# Computer_Power_Relay_-_Merge.net
KiCad netlist of a schematic drawn in EAGLE
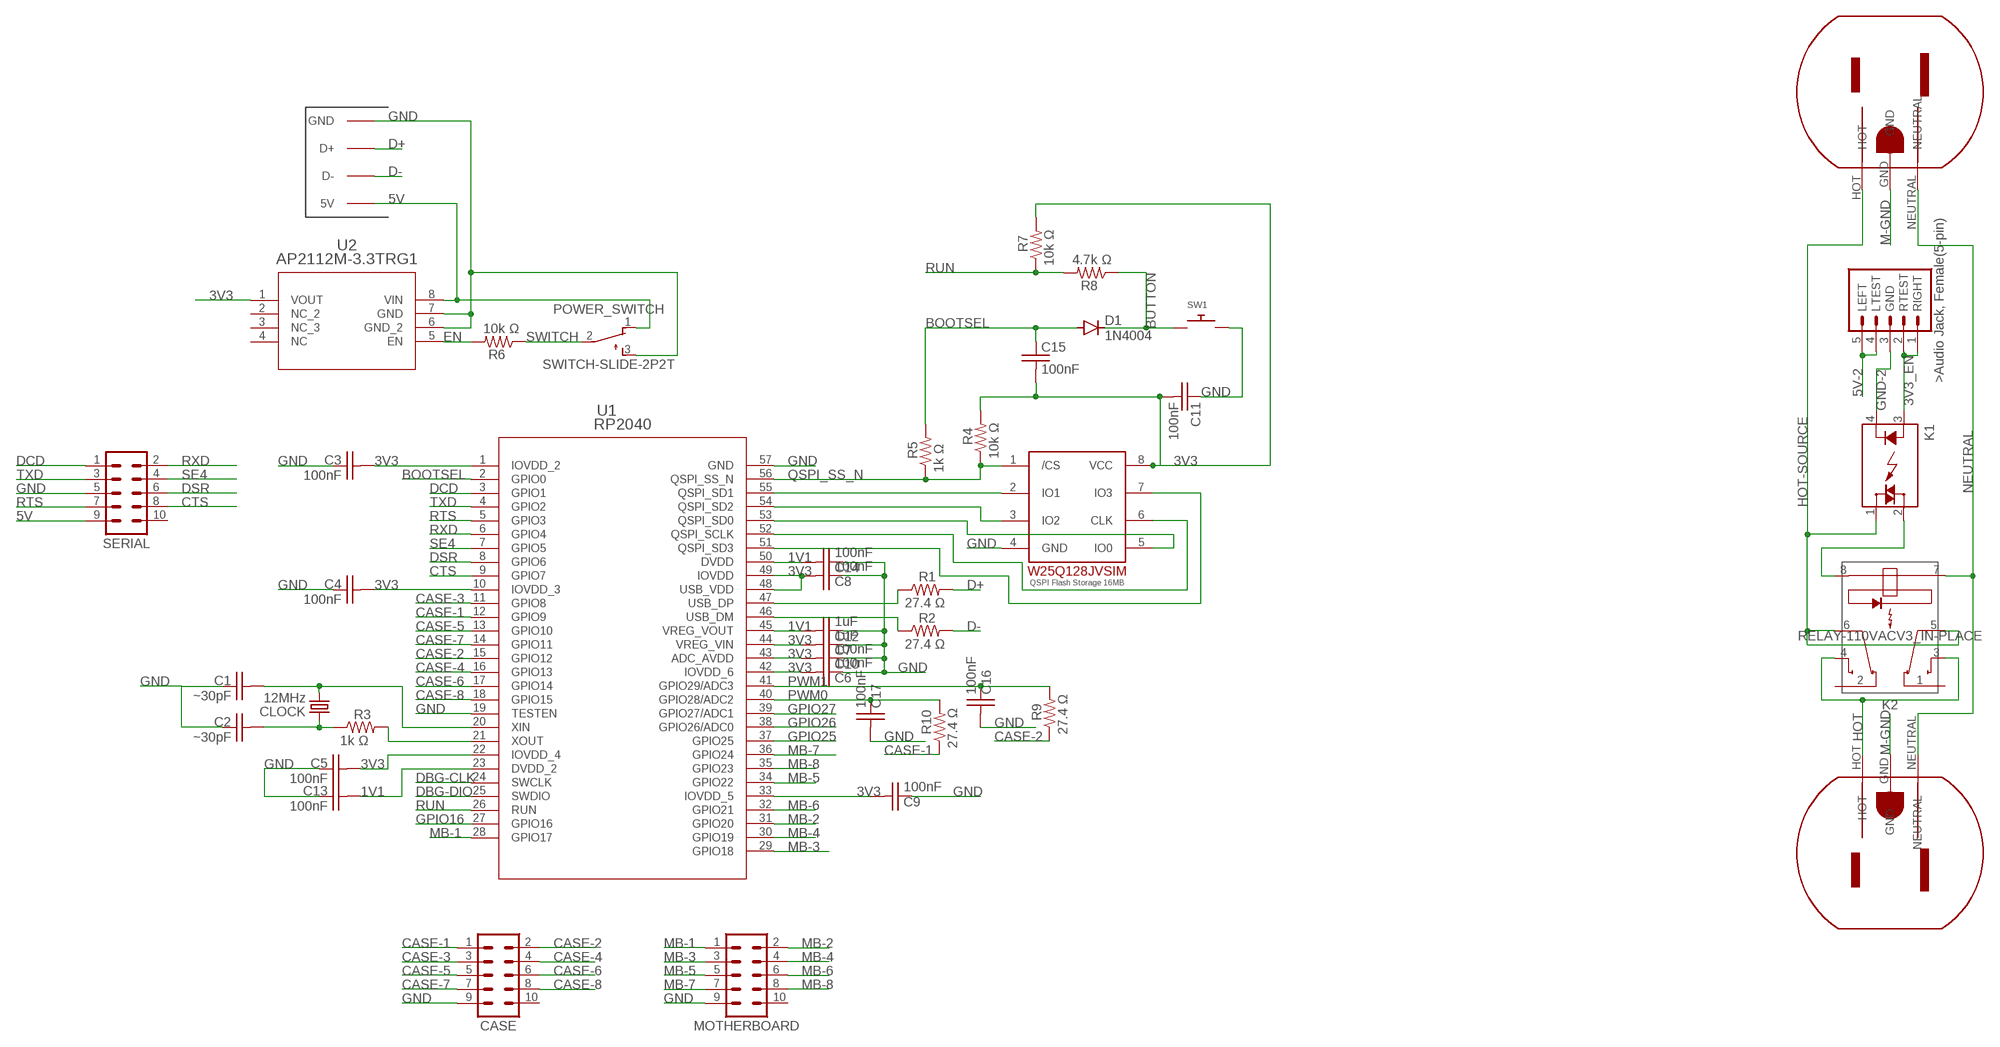
[diagram p0: schematic, sheet 1]

(export (version "E")
  (design (tool "Eeschema 10.0.6"))
  (components
    (comp (ref "C1")
      (value "~30pF")
      (footprint "eagle-import:C0402K")
      (libsource (lib "eagle-import") (part "CAP-NONPOL-USC0402K"))
    )
    (comp (ref "C2")
      (value "~30pF")
      (footprint "eagle-import:C0402K")
      (libsource (lib "eagle-import") (part "CAP-NONPOL-USC0402K"))
    )
    (comp (ref "C3")
      (value "100nF")
      (footprint "eagle-import:C0402K")
      (libsource (lib "eagle-import") (part "CAP-NONPOL-USC0402K"))
    )
    (comp (ref "C4")
      (value "100nF")
      (footprint "eagle-import:C0402K")
      (libsource (lib "eagle-import") (part "CAP-NONPOL-USC0402K"))
    )
    (comp (ref "C5")
      (value "100nF")
      (footprint "eagle-import:C0402K")
      (libsource (lib "eagle-import") (part "CAP-NONPOL-USC0402K"))
    )
    (comp (ref "C6")
      (value "100nF")
      (footprint "eagle-import:C0402K")
      (libsource (lib "eagle-import") (part "CAP-NONPOL-USC0402K"))
    )
    (comp (ref "C7")
      (value "1uF")
      (footprint "eagle-import:C0402K")
      (libsource (lib "eagle-import") (part "CAP-NONPOL-USC0402K"))
    )
    (comp (ref "C8")
      (value "100nF")
      (footprint "eagle-import:C0402K")
      (libsource (lib "eagle-import") (part "CAP-NONPOL-USC0402K"))
    )
    (comp (ref "C9")
      (value "100nF")
      (footprint "eagle-import:C0402K")
      (libsource (lib "eagle-import") (part "CAP-NONPOL-USC0402K"))
    )
    (comp (ref "C10")
      (value "100nF")
      (footprint "eagle-import:C0402K")
      (libsource (lib "eagle-import") (part "CAP-NONPOL-USC0402K"))
    )
    (comp (ref "C11")
      (value "100nF")
      (footprint "eagle-import:C0402K")
      (libsource (lib "eagle-import") (part "CAP-NONPOL-USC0402K"))
    )
    (comp (ref "C12")
      (value "1uF")
      (footprint "eagle-import:C0402K")
      (libsource (lib "eagle-import") (part "CAP-NONPOL-USC0402K"))
    )
    (comp (ref "C13")
      (value "100nF")
      (footprint "eagle-import:C0402K")
      (libsource (lib "eagle-import") (part "CAP-NONPOL-USC0402K"))
    )
    (comp (ref "C14")
      (value "100nF")
      (footprint "eagle-import:C0402K")
      (libsource (lib "eagle-import") (part "CAP-NONPOL-USC0402K"))
    )
    (comp (ref "C15")
      (value "100nF")
      (footprint "eagle-import:C0402K")
      (libsource (lib "eagle-import") (part "CAP-NONPOL-USC0402K"))
    )
    (comp (ref "C16")
      (value "100nF")
      (footprint "eagle-import:C0402K")
      (libsource (lib "eagle-import") (part "CAP-NONPOL-USC0402K"))
    )
    (comp (ref "C17")
      (value "100nF")
      (footprint "eagle-import:C0402K")
      (libsource (lib "eagle-import") (part "CAP-NONPOL-USC0402K"))
    )
    (comp (ref "CASE")
      (value "MA05-2")
      (footprint "eagle-import:MA05-2")
      (libsource (lib "eagle-import") (part "MA05-2"))
    )
    (comp (ref "CLOCK")
      (value "12MHz")
      (footprint "eagle-import:HC49_S")
      (libsource (lib "eagle-import") (part "CRYSTALHC49S"))
    )
    (comp (ref "D1")
      (value "1N4004")
      (footprint "eagle-import:DO41-10")
      (libsource (lib "eagle-import") (part "1N4004"))
    )
    (comp (ref "K1")
      (value "RELAY-3V3DC-110VAC012")
      (footprint "eagle-import:RELAY-3V3-110V")
      (fields (field (name "MPN") "ACV33012"))
      (libsource (lib "eagle-import") (part "RELAY-3V3DC-110VAC012"))
    )
    (comp (ref "K2")
      (value "RELAY-110VACV3_IN-PLACE")
      (footprint "eagle-import:RELAY-110VAC-V3")
      (libsource (lib "eagle-import") (part "RELAY-110VACV3_IN-PLACE"))
    )
    (comp (ref "MOTHERBOARD")
      (value "MA05-2")
      (footprint "eagle-import:MA05-2")
      (libsource (lib "eagle-import") (part "MA05-2"))
    )
    (comp (ref "POWER_SWITCH")
      (value "SWITCH-SLIDE-2P2T")
      (footprint "eagle-import:SWITCH-SLIDE-2P2T")
      (libsource (lib "eagle-import") (part "SWITCH-SLIDE-2P2T"))
    )
    (comp (ref "R1")
      (value "27.4 Ω")
      (footprint "eagle-import:R0603")
      (libsource (lib "eagle-import") (part "R-US_R0603"))
    )
    (comp (ref "R2")
      (value "27.4 Ω")
      (footprint "eagle-import:R0603")
      (libsource (lib "eagle-import") (part "R-US_R0603"))
    )
    (comp (ref "R3")
      (value "1k Ω")
      (footprint "eagle-import:R0603")
      (libsource (lib "eagle-import") (part "R-US_R0603"))
    )
    (comp (ref "R4")
      (value "10k Ω")
      (footprint "eagle-import:R0603")
      (libsource (lib "eagle-import") (part "R-US_R0603"))
    )
    (comp (ref "R5")
      (value "1k Ω")
      (footprint "eagle-import:R0603")
      (libsource (lib "eagle-import") (part "R-US_R0603"))
    )
    (comp (ref "R6")
      (value "10k Ω")
      (footprint "eagle-import:R0603")
      (libsource (lib "eagle-import") (part "R-US_R0603"))
    )
    (comp (ref "R7")
      (value "10k Ω")
      (footprint "eagle-import:R0603")
      (libsource (lib "eagle-import") (part "R-US_R0603"))
    )
    (comp (ref "R8")
      (value "4.7k Ω")
      (footprint "eagle-import:R0603")
      (libsource (lib "eagle-import") (part "R-US_R0603"))
    )
    (comp (ref "R9")
      (value "27.4 Ω")
      (footprint "eagle-import:R0603")
      (libsource (lib "eagle-import") (part "R-US_R0603"))
    )
    (comp (ref "R10")
      (value "27.4 Ω")
      (footprint "eagle-import:R0603")
      (libsource (lib "eagle-import") (part "R-US_R0603"))
    )
    (comp (ref "SERIAL")
      (value "MA05-2")
      (footprint "eagle-import:MA05-2")
      (libsource (lib "eagle-import") (part "MA05-2"))
    )
    (comp (ref "SW1")
      (value "SWITCH_PUSHBUTTONSOFTTOUCHSMD_SJ")
      (footprint "eagle-import:PUSHBUTTON_TH")
      (libsource (lib "eagle-import") (part "SWITCH_PUSHBUTTONSOFTTOUCHSMD_SJ"))
    )
    (comp (ref "U$1")
      (value "W25Q128JVSIM-ND__QSPI-FLASH")
      (footprint "eagle-import:SO08")
      (libsource (lib "eagle-import") (part "W25Q128JVSIM-ND__QSPI-FLASH"))
    )
    (comp (ref "U$2")
      (value "PCB_USB")
      (footprint "eagle-import:PCB_USB")
      (libsource (lib "eagle-import") (part "PCB_USB"))
    )
    (comp (ref "U$3")
      (value "MAINS-POWER-OUTLET3-PIN")
      (footprint "eagle-import:3-PIN-POWER")
      (libsource (lib "eagle-import") (part "MAINS-POWER-OUTLET3-PIN"))
    )
    (comp (ref "U$4")
      (value "MAINS-POWER-OUTLET3-PIN")
      (footprint "eagle-import:3-PIN-POWER")
      (libsource (lib "eagle-import") (part "MAINS-POWER-OUTLET3-PIN"))
    )
    (comp (ref "U$5")
      (value "AUDIO_JACK_FEMALE_5-PIN")
      (footprint "eagle-import:AUDIO_JACK_FEMALE_5-PIN")
      (libsource (lib "eagle-import") (part "AUDIO_JACK_FEMALE_5-PIN"))
    )
    (comp (ref "U1")
      (value "RP2040")
      (footprint "eagle-import:IC57_RP2040")
      (fields
        (field (name "MANUFACTURER_PART_NUMBER") "SC0908(7)")
        (field (name "COPYRIGHT") "Copyright (C) 2022 Ultra Librarian. All rights reserved.")
      )
      (libsource (lib "eagle-import") (part "RP2040"))
    )
    (comp (ref "U2")
      (value "AP2112M-3.3TRG1")
      (footprint "eagle-import:AP2112M-3.3TRG1_DIO")
      (fields (field (name "COPYRIGHT") "Copyright (C) 2022 Ultra Librarian. All rights reserved."))
      (libsource (lib "eagle-import") (part "AP2112M-3.3TRG1"))
    )
  )
  (nets
    (net (code "1") (name "/1V1") (class "Default")
      (node (ref "C12") (pin "2") (pinfunction "2_2") (pintype "passive"))
      (node (ref "C13") (pin "2") (pinfunction "2_2") (pintype "passive"))
      (node (ref "C14") (pin "2") (pinfunction "2_2") (pintype "passive"))
      (node (ref "U1") (pin "23") (pinfunction "DVDD_2_23") (pintype "power_in"))
      (node (ref "U1") (pin "45") (pinfunction "VREG_VOUT_45") (pintype "output"))
      (node (ref "U1") (pin "50") (pinfunction "DVDD_50") (pintype "power_in"))
    )
    (net (code "2") (name "/3V3") (class "Default")
      (node (ref "C10") (pin "2") (pinfunction "2_2") (pintype "passive"))
      (node (ref "C11") (pin "2") (pinfunction "2_2") (pintype "passive"))
      (node (ref "C15") (pin "2") (pinfunction "2_2") (pintype "passive"))
      (node (ref "C3") (pin "2") (pinfunction "2_2") (pintype "passive"))
      (node (ref "C4") (pin "2") (pinfunction "2_2") (pintype "passive"))
      (node (ref "C5") (pin "2") (pinfunction "2_2") (pintype "passive"))
      (node (ref "C6") (pin "2") (pinfunction "2_2") (pintype "passive"))
      (node (ref "C7") (pin "2") (pinfunction "2_2") (pintype "passive"))
      (node (ref "C8") (pin "2") (pinfunction "2_2") (pintype "passive"))
      (node (ref "C9") (pin "2") (pinfunction "2_2") (pintype "passive"))
      (node (ref "R4") (pin "2") (pinfunction "2_2") (pintype "passive"))
      (node (ref "R7") (pin "2") (pinfunction "2_2") (pintype "passive"))
      (node (ref "U$1") (pin "8") (pinfunction "VCC_8") (pintype "power_in"))
      (node (ref "U1") (pin "1") (pinfunction "IOVDD_2_1") (pintype "power_in"))
      (node (ref "U1") (pin "10") (pinfunction "IOVDD_3_10") (pintype "power_in"))
      (node (ref "U1") (pin "22") (pinfunction "IOVDD_4_22") (pintype "power_in"))
      (node (ref "U1") (pin "33") (pinfunction "IOVDD_5_33") (pintype "power_in"))
      (node (ref "U1") (pin "42") (pinfunction "IOVDD_6_42") (pintype "power_in"))
      (node (ref "U1") (pin "43") (pinfunction "ADC_AVDD_43") (pintype "power_in"))
      (node (ref "U1") (pin "44") (pinfunction "VREG_VIN_44") (pintype "passive"))
      (node (ref "U1") (pin "48") (pinfunction "USB_VDD_48") (pintype "power_in"))
      (node (ref "U1") (pin "49") (pinfunction "IOVDD_49") (pintype "power_in"))
      (node (ref "U2") (pin "1") (pinfunction "VOUT_1") (pintype "output"))
    )
    (net (code "3") (name "/3V3_EN") (class "Default")
      (node (ref "K1") (pin "3") (pinfunction "3_3") (pintype "passive"))
      (node (ref "U$5") (pin "1") (pinfunction "RIGHT_1") (pintype "input"))
      (node (ref "U$5") (pin "2") (pinfunction "RTEST_2") (pintype "output"))
    )
    (net (code "4") (name "/5V") (class "Default")
      (node (ref "POWER_SWITCH") (pin "1") (pinfunction "O_1") (pintype "passive"))
      (node (ref "SERIAL") (pin "9") (pinfunction "9_9") (pintype "passive"))
      (node (ref "U$2") (pin "5V") (pinfunction "5V_5V") (pintype "bidirectional"))
      (node (ref "U$2") (pin "5V_2") (pinfunction "5V_5V_2") (pintype "bidirectional"))
      (node (ref "U2") (pin "8") (pinfunction "VIN_8") (pintype "power_in"))
    )
    (net (code "5") (name "/5V-2") (class "Default")
      (node (ref "U$5") (pin "4") (pinfunction "LTEST_4") (pintype "output"))
      (node (ref "U$5") (pin "5") (pinfunction "LEFT_5") (pintype "input"))
    )
    (net (code "6") (name "/BOOTSEL") (class "Default")
      (node (ref "C15") (pin "1") (pinfunction "1_1") (pintype "passive"))
      (node (ref "D1") (pin "A") (pinfunction "A_A") (pintype "passive"))
      (node (ref "R5") (pin "2") (pinfunction "2_2") (pintype "passive"))
      (node (ref "U1") (pin "2") (pinfunction "GPIO0_2") (pintype "bidirectional"))
    )
    (net (code "7") (name "/BUTTON") (class "Default")
      (node (ref "D1") (pin "C") (pinfunction "C_C") (pintype "passive"))
      (node (ref "R8") (pin "1") (pinfunction "1_1") (pintype "passive"))
      (node (ref "SW1") (pin "P$1") (pinfunction "P$1_P$1") (pintype "passive"))
    )
    (net (code "8") (name "/CASE-1") (class "Default")
      (node (ref "CASE") (pin "1") (pinfunction "1_1") (pintype "passive"))
      (node (ref "R10") (pin "1") (pinfunction "1_1") (pintype "passive"))
      (node (ref "U1") (pin "12") (pinfunction "GPIO9_12") (pintype "bidirectional"))
    )
    (net (code "9") (name "/CASE-2") (class "Default")
      (node (ref "CASE") (pin "2") (pinfunction "2_2") (pintype "passive"))
      (node (ref "R9") (pin "1") (pinfunction "1_1") (pintype "passive"))
      (node (ref "U1") (pin "15") (pinfunction "GPIO12_15") (pintype "bidirectional"))
    )
    (net (code "10") (name "/CASE-3") (class "Default")
      (node (ref "CASE") (pin "3") (pinfunction "3_3") (pintype "passive"))
      (node (ref "U1") (pin "11") (pinfunction "GPIO8_11") (pintype "bidirectional"))
    )
    (net (code "11") (name "/CASE-4") (class "Default")
      (node (ref "CASE") (pin "4") (pinfunction "4_4") (pintype "passive"))
      (node (ref "U1") (pin "16") (pinfunction "GPIO13_16") (pintype "bidirectional"))
    )
    (net (code "12") (name "/CASE-5") (class "Default")
      (node (ref "CASE") (pin "5") (pinfunction "5_5") (pintype "passive"))
      (node (ref "U1") (pin "13") (pinfunction "GPIO10_13") (pintype "bidirectional"))
    )
    (net (code "13") (name "/CASE-6") (class "Default")
      (node (ref "CASE") (pin "6") (pinfunction "6_6") (pintype "passive"))
      (node (ref "U1") (pin "17") (pinfunction "GPIO14_17") (pintype "bidirectional"))
    )
    (net (code "14") (name "/CASE-7") (class "Default")
      (node (ref "CASE") (pin "7") (pinfunction "7_7") (pintype "passive"))
      (node (ref "U1") (pin "14") (pinfunction "GPIO11_14") (pintype "bidirectional"))
    )
    (net (code "15") (name "/CASE-8") (class "Default")
      (node (ref "CASE") (pin "8") (pinfunction "8_8") (pintype "passive"))
      (node (ref "U1") (pin "18") (pinfunction "GPIO15_18") (pintype "bidirectional"))
    )
    (net (code "16") (name "/CTS") (class "Default")
      (node (ref "SERIAL") (pin "8") (pinfunction "8_8") (pintype "passive"))
      (node (ref "U1") (pin "9") (pinfunction "GPIO7_9") (pintype "bidirectional"))
    )
    (net (code "17") (name "/D+") (class "Default")
      (node (ref "R1") (pin "2") (pinfunction "2_2") (pintype "passive"))
      (node (ref "U$2") (pin "D+") (pinfunction "D+_D+") (pintype "bidirectional"))
      (node (ref "U$2") (pin "D+_2") (pinfunction "D+_D+_2") (pintype "bidirectional"))
    )
    (net (code "18") (name "/D-") (class "Default")
      (node (ref "R2") (pin "2") (pinfunction "2_2") (pintype "passive"))
      (node (ref "U$2") (pin "D-") (pinfunction "D-_D-") (pintype "bidirectional"))
      (node (ref "U$2") (pin "D-_2") (pinfunction "D-_D-_2") (pintype "bidirectional"))
    )
    (net (code "19") (name "/DBG-CLK") (class "Default")
      (node (ref "U1") (pin "24") (pinfunction "SWCLK_24") (pintype "passive"))
    )
    (net (code "20") (name "/DBG-DIO") (class "Default")
      (node (ref "U1") (pin "25") (pinfunction "SWDIO_25") (pintype "passive"))
    )
    (net (code "21") (name "/DCD") (class "Default")
      (node (ref "SERIAL") (pin "1") (pinfunction "1_1") (pintype "passive"))
      (node (ref "U1") (pin "3") (pinfunction "GPIO1_3") (pintype "bidirectional"))
    )
    (net (code "22") (name "/DSR") (class "Default")
      (node (ref "SERIAL") (pin "6") (pinfunction "6_6") (pintype "passive"))
      (node (ref "U1") (pin "8") (pinfunction "GPIO6_8") (pintype "bidirectional"))
    )
    (net (code "23") (name "/EN") (class "Default")
      (node (ref "R6") (pin "2") (pinfunction "2_2") (pintype "passive"))
      (node (ref "U2") (pin "5") (pinfunction "EN_5") (pintype "passive"))
    )
    (net (code "24") (name "/GND") (class "Default")
      (node (ref "C1") (pin "1") (pinfunction "1_1") (pintype "passive"))
      (node (ref "C10") (pin "1") (pinfunction "1_1") (pintype "passive"))
      (node (ref "C11") (pin "1") (pinfunction "1_1") (pintype "passive"))
      (node (ref "C12") (pin "1") (pinfunction "1_1") (pintype "passive"))
      (node (ref "C13") (pin "1") (pinfunction "1_1") (pintype "passive"))
      (node (ref "C14") (pin "1") (pinfunction "1_1") (pintype "passive"))
      (node (ref "C16") (pin "2") (pinfunction "2_2") (pintype "passive"))
      (node (ref "C17") (pin "2") (pinfunction "2_2") (pintype "passive"))
      (node (ref "C2") (pin "1") (pinfunction "1_1") (pintype "passive"))
      (node (ref "C3") (pin "1") (pinfunction "1_1") (pintype "passive"))
      (node (ref "C4") (pin "1") (pinfunction "1_1") (pintype "passive"))
      (node (ref "C5") (pin "1") (pinfunction "1_1") (pintype "passive"))
      (node (ref "C6") (pin "1") (pinfunction "1_1") (pintype "passive"))
      (node (ref "C7") (pin "1") (pinfunction "1_1") (pintype "passive"))
      (node (ref "C8") (pin "1") (pinfunction "1_1") (pintype "passive"))
      (node (ref "C9") (pin "1") (pinfunction "1_1") (pintype "passive"))
      (node (ref "CASE") (pin "9") (pinfunction "9_9") (pintype "passive"))
      (node (ref "MOTHERBOARD") (pin "9") (pinfunction "9_9") (pintype "passive"))
      (node (ref "POWER_SWITCH") (pin "3") (pinfunction "S_3") (pintype "passive"))
      (node (ref "SERIAL") (pin "5") (pinfunction "5_5") (pintype "passive"))
      (node (ref "SW1") (pin "P$2") (pinfunction "P$2_P$2") (pintype "passive"))
      (node (ref "U$1") (pin "4") (pinfunction "GND_4") (pintype "power_in"))
      (node (ref "U$2") (pin "GND") (pinfunction "GND_GND") (pintype "bidirectional"))
      (node (ref "U$2") (pin "GND_2") (pinfunction "GND_GND_2") (pintype "bidirectional"))
      (node (ref "U1") (pin "19") (pinfunction "TESTEN_19") (pintype "passive"))
      (node (ref "U1") (pin "57") (pinfunction "GND_57") (pintype "passive"))
      (node (ref "U2") (pin "6") (pinfunction "GND_2_6") (pintype "passive"))
      (node (ref "U2") (pin "7") (pinfunction "GND_7") (pintype "passive"))
    )
    (net (code "25") (name "/GND-2") (class "Default")
      (node (ref "K1") (pin "4") (pinfunction "4_4") (pintype "passive"))
      (node (ref "U$5") (pin "3") (pinfunction "GND_3") (pintype "power_in"))
    )
    (net (code "26") (name "/GPIO16") (class "Default")
      (node (ref "U1") (pin "27") (pinfunction "GPIO16_27") (pintype "bidirectional"))
    )
    (net (code "27") (name "/GPIO25") (class "Default")
      (node (ref "U1") (pin "37") (pinfunction "GPIO25_37") (pintype "bidirectional"))
    )
    (net (code "28") (name "/GPIO26") (class "Default")
      (node (ref "U1") (pin "38") (pinfunction "GPIO26/ADC0_38") (pintype "bidirectional"))
    )
    (net (code "29") (name "/GPIO27") (class "Default")
      (node (ref "U1") (pin "39") (pinfunction "GPIO27/ADC1_39") (pintype "bidirectional"))
    )
    (net (code "30") (name "/HOT") (class "Default")
      (node (ref "K2") (pin "3") (pinfunction "3_3") (pintype "bidirectional"))
      (node (ref "K2") (pin "4") (pinfunction "4_4") (pintype "bidirectional"))
      (node (ref "U$4") (pin "HOT") (pinfunction "HOT_HOT") (pintype "bidirectional"))
    )
    (net (code "31") (name "/HOT-SOURCE") (class "Default")
      (node (ref "K1") (pin "1") (pinfunction "1_1") (pintype "passive"))
      (node (ref "K2") (pin "5") (pinfunction "5_5") (pintype "bidirectional"))
      (node (ref "K2") (pin "6") (pinfunction "6_6") (pintype "bidirectional"))
      (node (ref "U$3") (pin "HOT") (pinfunction "HOT_HOT") (pintype "bidirectional"))
    )
    (net (code "32") (name "/M-GND") (class "Default")
      (node (ref "U$3") (pin "GND") (pinfunction "GND_GND") (pintype "bidirectional"))
      (node (ref "U$4") (pin "GND") (pinfunction "GND_GND") (pintype "bidirectional"))
    )
    (net (code "33") (name "/MB-1") (class "Default")
      (node (ref "MOTHERBOARD") (pin "1") (pinfunction "1_1") (pintype "passive"))
      (node (ref "U1") (pin "28") (pinfunction "GPIO17_28") (pintype "bidirectional"))
    )
    (net (code "34") (name "/MB-2") (class "Default")
      (node (ref "MOTHERBOARD") (pin "2") (pinfunction "2_2") (pintype "passive"))
      (node (ref "U1") (pin "31") (pinfunction "GPIO20_31") (pintype "bidirectional"))
    )
    (net (code "35") (name "/MB-3") (class "Default")
      (node (ref "MOTHERBOARD") (pin "3") (pinfunction "3_3") (pintype "passive"))
      (node (ref "U1") (pin "29") (pinfunction "GPIO18_29") (pintype "bidirectional"))
    )
    (net (code "36") (name "/MB-4") (class "Default")
      (node (ref "MOTHERBOARD") (pin "4") (pinfunction "4_4") (pintype "passive"))
      (node (ref "U1") (pin "30") (pinfunction "GPIO19_30") (pintype "bidirectional"))
    )
    (net (code "37") (name "/MB-5") (class "Default")
      (node (ref "MOTHERBOARD") (pin "5") (pinfunction "5_5") (pintype "passive"))
      (node (ref "U1") (pin "34") (pinfunction "GPIO22_34") (pintype "bidirectional"))
    )
    (net (code "38") (name "/MB-6") (class "Default")
      (node (ref "MOTHERBOARD") (pin "6") (pinfunction "6_6") (pintype "passive"))
      (node (ref "U1") (pin "32") (pinfunction "GPIO21_32") (pintype "bidirectional"))
    )
    (net (code "39") (name "/MB-7") (class "Default")
      (node (ref "MOTHERBOARD") (pin "7") (pinfunction "7_7") (pintype "passive"))
      (node (ref "U1") (pin "36") (pinfunction "GPIO24_36") (pintype "bidirectional"))
    )
    (net (code "40") (name "/MB-8") (class "Default")
      (node (ref "MOTHERBOARD") (pin "8") (pinfunction "8_8") (pintype "passive"))
      (node (ref "U1") (pin "35") (pinfunction "GPIO23_35") (pintype "bidirectional"))
    )
    (net (code "41") (name "/NEUTRAL") (class "Default")
      (node (ref "K2") (pin "7") (pinfunction "7_7") (pintype "passive"))
      (node (ref "U$3") (pin "NEUTRAL") (pinfunction "NEUTRAL_NEUTRAL") (pintype "bidirectional"))
      (node (ref "U$4") (pin "NEUTRAL") (pinfunction "NEUTRAL_NEUTRAL") (pintype "bidirectional"))
    )
    (net (code "42") (name "/PWM0") (class "Default")
      (node (ref "C17") (pin "1") (pinfunction "1_1") (pintype "passive"))
      (node (ref "R10") (pin "2") (pinfunction "2_2") (pintype "passive"))
      (node (ref "U1") (pin "40") (pinfunction "GPIO28/ADC2_40") (pintype "bidirectional"))
    )
    (net (code "43") (name "/PWM1") (class "Default")
      (node (ref "C16") (pin "1") (pinfunction "1_1") (pintype "passive"))
      (node (ref "R9") (pin "2") (pinfunction "2_2") (pintype "passive"))
      (node (ref "U1") (pin "41") (pinfunction "GPIO29/ADC3_41") (pintype "bidirectional"))
    )
    (net (code "44") (name "/QSPI_SS_N") (class "Default")
      (node (ref "R4") (pin "1") (pinfunction "1_1") (pintype "passive"))
      (node (ref "R5") (pin "1") (pinfunction "1_1") (pintype "passive"))
      (node (ref "U$1") (pin "1") (pinfunction "/CS_1") (pintype "input"))
      (node (ref "U1") (pin "56") (pinfunction "QSPI_SS_N_56") (pintype "passive"))
    )
    (net (code "45") (name "/RTS") (class "Default")
      (node (ref "SERIAL") (pin "7") (pinfunction "7_7") (pintype "passive"))
      (node (ref "U1") (pin "5") (pinfunction "GPIO3_5") (pintype "bidirectional"))
    )
    (net (code "46") (name "/RUN") (class "Default")
      (node (ref "R7") (pin "1") (pinfunction "1_1") (pintype "passive"))
      (node (ref "R8") (pin "2") (pinfunction "2_2") (pintype "passive"))
      (node (ref "U1") (pin "26") (pinfunction "RUN_26") (pintype "passive"))
    )
    (net (code "47") (name "/RXD") (class "Default")
      (node (ref "SERIAL") (pin "2") (pinfunction "2_2") (pintype "passive"))
      (node (ref "U1") (pin "6") (pinfunction "GPIO4_6") (pintype "bidirectional"))
    )
    (net (code "48") (name "/SE4") (class "Default")
      (node (ref "SERIAL") (pin "4") (pinfunction "4_4") (pintype "passive"))
      (node (ref "U1") (pin "7") (pinfunction "GPIO5_7") (pintype "bidirectional"))
    )
    (net (code "49") (name "/SWITCH") (class "Default")
      (node (ref "POWER_SWITCH") (pin "2") (pinfunction "P_2") (pintype "passive"))
      (node (ref "R6") (pin "1") (pinfunction "1_1") (pintype "passive"))
    )
    (net (code "50") (name "/TXD") (class "Default")
      (node (ref "SERIAL") (pin "3") (pinfunction "3_3") (pintype "passive"))
      (node (ref "U1") (pin "4") (pinfunction "GPIO2_4") (pintype "bidirectional"))
    )
    (net (code "51") (name "Net-(C2-Pad2)") (class "Default")
      (node (ref "C2") (pin "2") (pinfunction "2_2") (pintype "passive"))
      (node (ref "CLOCK") (pin "2") (pinfunction "2_2") (pintype "passive"))
      (node (ref "R3") (pin "1") (pinfunction "1_1") (pintype "passive"))
    )
    (net (code "52") (name "Net-(K1-Pad2)") (class "Default")
      (node (ref "K1") (pin "2") (pinfunction "2_2") (pintype "passive"))
      (node (ref "K2") (pin "8") (pinfunction "8_8") (pintype "passive"))
    )
    (net (code "53") (name "Net-(U$1-CLK)") (class "Default")
      (node (ref "U$1") (pin "6") (pinfunction "CLK_6") (pintype "bidirectional"))
      (node (ref "U1") (pin "52") (pinfunction "QSPI_SCLK_52") (pintype "passive"))
    )
    (net (code "54") (name "Net-(U$1-IO0)") (class "Default")
      (node (ref "U$1") (pin "5") (pinfunction "IO0_5") (pintype "bidirectional"))
      (node (ref "U1") (pin "53") (pinfunction "QSPI_SD0_53") (pintype "bidirectional"))
    )
    (net (code "55") (name "Net-(U$1-IO1)") (class "Default")
      (node (ref "U$1") (pin "2") (pinfunction "IO1_2") (pintype "bidirectional"))
      (node (ref "U1") (pin "55") (pinfunction "QSPI_SD1_55") (pintype "bidirectional"))
    )
    (net (code "56") (name "Net-(U$1-IO2)") (class "Default")
      (node (ref "U$1") (pin "3") (pinfunction "IO2_3") (pintype "bidirectional"))
      (node (ref "U1") (pin "54") (pinfunction "QSPI_SD2_54") (pintype "bidirectional"))
    )
    (net (code "57") (name "Net-(U$1-IO3)") (class "Default")
      (node (ref "U$1") (pin "7") (pinfunction "IO3_7") (pintype "output"))
      (node (ref "U1") (pin "51") (pinfunction "QSPI_SD3_51") (pintype "bidirectional"))
    )
    (net (code "58") (name "Net-(U1-USB_DM)") (class "Default")
      (node (ref "R2") (pin "1") (pinfunction "1_1") (pintype "passive"))
      (node (ref "U1") (pin "46") (pinfunction "USB_DM_46") (pintype "passive"))
    )
    (net (code "59") (name "Net-(U1-USB_DP)") (class "Default")
      (node (ref "R1") (pin "1") (pinfunction "1_1") (pintype "passive"))
      (node (ref "U1") (pin "47") (pinfunction "USB_DP_47") (pintype "passive"))
    )
    (net (code "60") (name "Net-(U1-XIN)") (class "Default")
      (node (ref "C1") (pin "2") (pinfunction "2_2") (pintype "passive"))
      (node (ref "CLOCK") (pin "1") (pinfunction "1_1") (pintype "passive"))
      (node (ref "U1") (pin "20") (pinfunction "XIN_20") (pintype "passive"))
    )
    (net (code "61") (name "Net-(U1-XOUT)") (class "Default")
      (node (ref "R3") (pin "2") (pinfunction "2_2") (pintype "passive"))
      (node (ref "U1") (pin "21") (pinfunction "XOUT_21") (pintype "output"))
    )
    (net (code "62") (name "unconnected-(CASE-Pad10)") (class "Default")
      (node (ref "CASE") (pin "10") (pinfunction "10_10") (pintype "passive"))
    )
    (net (code "63") (name "unconnected-(K2-Pad1)") (class "Default")
      (node (ref "K2") (pin "1") (pinfunction "1_1") (pintype "bidirectional"))
    )
    (net (code "64") (name "unconnected-(K2-Pad2)") (class "Default")
      (node (ref "K2") (pin "2") (pinfunction "2_2") (pintype "bidirectional"))
    )
    (net (code "65") (name "unconnected-(MOTHERBOARD-Pad10)") (class "Default")
      (node (ref "MOTHERBOARD") (pin "10") (pinfunction "10_10") (pintype "passive"))
    )
    (net (code "66") (name "unconnected-(SERIAL-Pad10)") (class "Default")
      (node (ref "SERIAL") (pin "10") (pinfunction "10_10") (pintype "passive"))
    )
    (net (code "67") (name "unconnected-(U2-NC-Pad4)") (class "Default")
      (node (ref "U2") (pin "4") (pinfunction "NC_4") (pintype "no_connect"))
    )
    (net (code "68") (name "unconnected-(U2-NC_2-Pad2)") (class "Default")
      (node (ref "U2") (pin "2") (pinfunction "NC_2_2") (pintype "no_connect"))
    )
    (net (code "69") (name "unconnected-(U2-NC_3-Pad3)") (class "Default")
      (node (ref "U2") (pin "3") (pinfunction "NC_3_3") (pintype "no_connect"))
    )
  )
)
